# SpaceVNXBaseBoard.net
KiCad netlist of a schematic drawn in Altium Designer
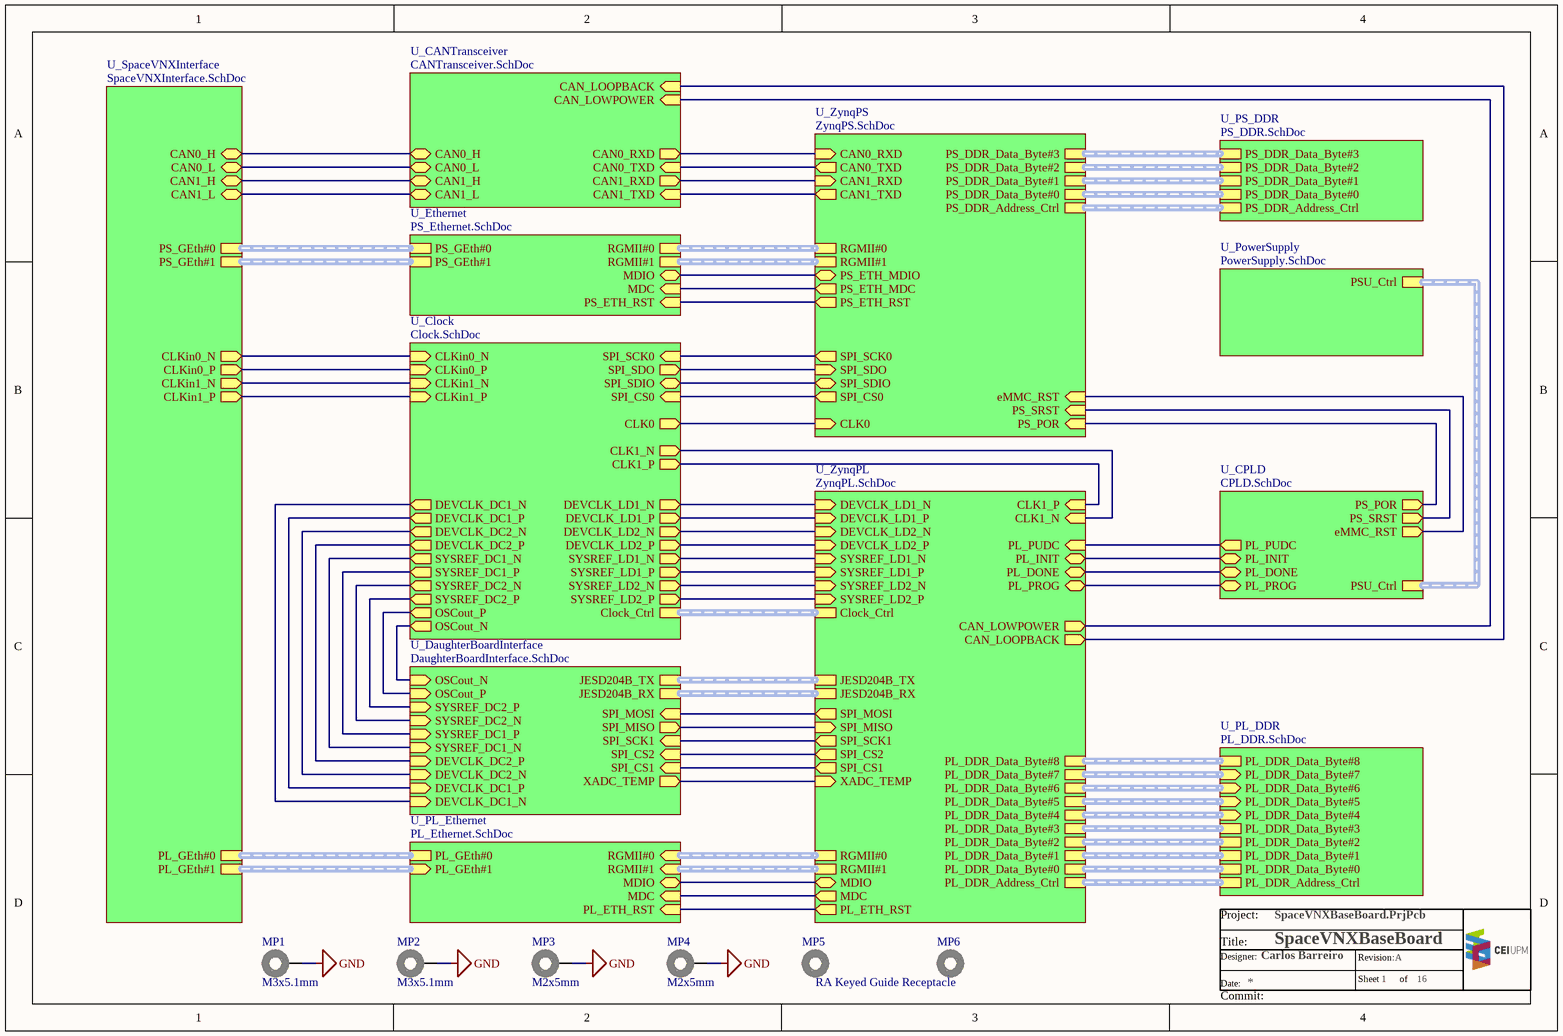
[diagram p0: SpaceVNXBaseBoard.SchDoc]

(export (version "E")
  (design (tool "Eeschema 10.0.6"))
  (components
    (comp (ref "MP1")
      (value "M3x5.1mm")
      (footprint "9775051360")
      (description "WA-SMSR SMT Steel Spacer Reverse with internal Thread M3, Length 5.1mm")
      (fields
        (field (name "MANUFACTURER PART NUMBER") "9775051360")
        (field (name "MANUFACTURER") "Wurth Elektronik")
      )
      (libsource (lib "SpaceVNX") (part "9775051360"))
    )
    (comp (ref "MP2")
      (value "M3x5.1mm")
      (footprint "9775051360")
      (description "WA-SMSR SMT Steel Spacer Reverse with internal Thread M3, Length 5.1mm")
      (fields
        (field (name "MANUFACTURER PART NUMBER") "9775051360")
        (field (name "MANUFACTURER") "Wurth Elektronik")
      )
      (libsource (lib "SpaceVNX") (part "9775051360"))
    )
    (comp (ref "MP3")
      (value "M2x5mm")
      (footprint "9774050243")
      (description "WA-SMSI SMT Steel Spacer, internal Thread, OD 4.35mm, M2x5mm")
      (fields
        (field (name "MANUFACTURER PART NUMBER") "9774050243")
        (field (name "MANUFACTURER") "Wurth Elektronik")
      )
      (libsource (lib "SpaceVNX") (part "9774050243"))
    )
    (comp (ref "MP4")
      (value "M2x5mm")
      (footprint "9774050243")
      (description "WA-SMSI SMT Steel Spacer, internal Thread, OD 4.35mm, M2x5mm")
      (fields
        (field (name "MANUFACTURER PART NUMBER") "9774050243")
        (field (name "MANUFACTURER") "Wurth Elektronik")
      )
      (libsource (lib "SpaceVNX") (part "9774050243"))
    )
    (comp (ref "MP5")
      (value "RA Keyed Guide Receptacle")
      (footprint "Guide Pin Receptacle")
      (description "Backplane Guide Hardware")
      (libsource (lib "SpaceVNX") (part "Vita74_Guide_Post"))
    )
    (comp (ref "MP6")
      (value "RA Keyed Guide Receptacle")
      (footprint "Guide Pin Receptacle")
      (description "Backplane Guide Hardware")
      (libsource (lib "SpaceVNX") (part "Vita74_Guide_Post"))
    )
  )
  (nets
    (net (code "86") (name "GND") (class "Default")
      (node (ref "MP1") (pin "1") (pinfunction "1_1") (pintype "passive"))
      (node (ref "MP2") (pin "1") (pinfunction "1_1") (pintype "passive"))
      (node (ref "MP3") (pin "1") (pinfunction "1_1") (pintype "passive"))
      (node (ref "MP4") (pin "1") (pinfunction "1_1") (pintype "passive"))
    )
  )
)
